# TPS_buckboost.net
KiCad netlist of a schematic drawn in Altium Designer
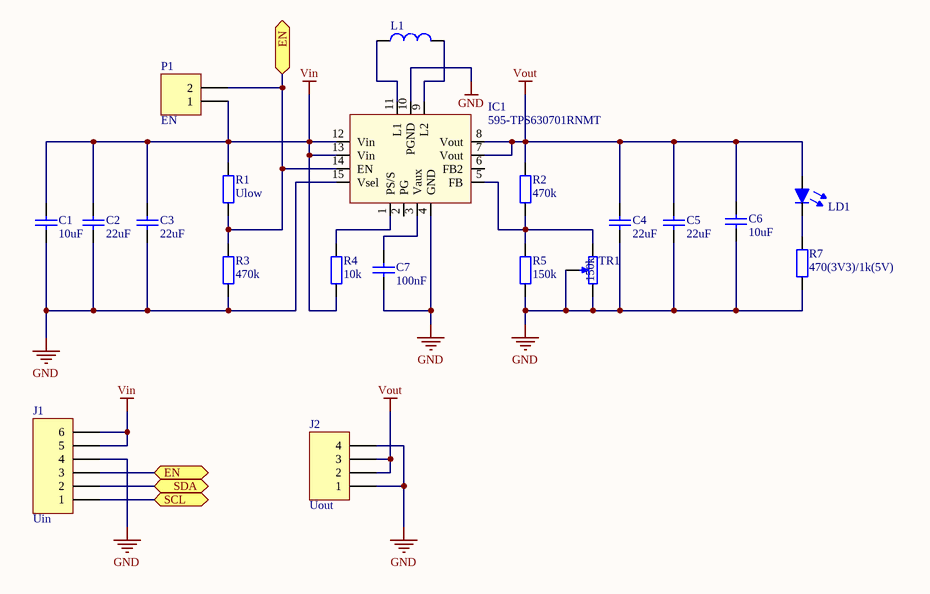
[diagram p0: TPS buckboost.SchDoc]

(export (version "E")
  (design (tool "Eeschema 10.0.6"))
  (components
    (comp (ref "C1")
      (value "10uF")
      (footprint "0805 CAP")
      (description "Capacitor")
      (fields (field (name "VOLTAGE") "10V"))
      (libsource (lib "IKSOR_LIB_main") (part "Capacitor NP"))
    )
    (comp (ref "C2")
      (value "22uF")
      (footprint "1210 CAP")
      (description "Capacitor")
      (fields (field (name "VOLTAGE") "10V"))
      (libsource (lib "IKSOR_LIB_main") (part "Capacitor NP"))
    )
    (comp (ref "C3")
      (value "22uF")
      (footprint "1210 CAP")
      (description "Capacitor")
      (fields (field (name "VOLTAGE") "10V"))
      (libsource (lib "IKSOR_LIB_main") (part "Capacitor NP"))
    )
    (comp (ref "C4")
      (value "22uF")
      (footprint "1210 CAP")
      (description "Capacitor NP")
      (fields (field (name "VOLTAGE") "10V") (field (name "Comment") "Capacitor"))
      (libsource (lib "IKSOR_LIB_main") (part "Capacitor NP"))
    )
    (comp (ref "C5")
      (value "22uF")
      (footprint "1210 CAP")
      (description "Capacitor NP")
      (fields (field (name "VOLTAGE") "10V") (field (name "Comment") "Capacitor"))
      (libsource (lib "IKSOR_LIB_main") (part "Capacitor NP"))
    )
    (comp (ref "C6")
      (value "10uF")
      (footprint "0805 CAP")
      (description "Capacitor")
      (libsource (lib "IKSOR_LIB_main") (part "Capacitor NP"))
    )
    (comp (ref "C7")
      (value "100nF")
      (footprint "0603 cap")
      (description "Capacitor")
      (fields (field (name "VOLTAGE") "10V"))
      (libsource (lib "IKSOR_LIB_main") (part "Capacitor NP"))
    )
    (comp (ref "IC1")
      (value "TPS63070/71")
      (footprint "VQFN TPS")
      (description "Buck-boost switcher")
      (fields (field (name "SUPPLIER PART NUMBER 1") "595-TPS630701RNMT"))
      (libsource (lib "IKSOR_LIB_main") (part "TPS63070/71"))
    )
    (comp (ref "J1")
      (value "Uin")
      (footprint "HDR1X6")
      (description "Header, 6-Pin")
      (fields (field (name "PUBLISHER") "Altium Limited"))
      (libsource (lib "Miscellaneous Connectors") (part "Header 6"))
    )
    (comp (ref "J2")
      (value "Uout")
      (footprint "HDR1X4")
      (description "Header, 4-Pin")
      (fields (field (name "PUBLISHER") "Altium Limited"))
      (libsource (lib "Miscellaneous Connectors") (part "Header 4"))
    )
    (comp (ref "L1")
      (value "Inductor")
      (footprint "FDSD0420-H")
      (description "Single coil")
      (libsource (lib "IKSOR_LIB_main") (part "Inductor"))
    )
    (comp (ref "LD1")
      (value "LED diode")
      (footprint "LED_0603")
      (description "LED")
      (libsource (lib "IKSOR_LIB_main") (part "LED diode"))
    )
    (comp (ref "P1")
      (value "EN")
      (footprint "HDR1X2")
      (description "Header, 2-Pin")
      (libsource (lib "Miscellaneous Connectors") (part "Header 2"))
    )
    (comp (ref "R1")
      (value "Ulow")
      (footprint "0603 RES")
      (description "NP")
      (fields (field (name "Comment") "Resistor generic"))
      (libsource (lib "IKSOR_LIB_main") (part "Resistor"))
    )
    (comp (ref "R2")
      (value "470k")
      (footprint "0603 RES")
      (description "Resistor SMD")
      (fields (field (name "Comment") "Resistor generic"))
      (libsource (lib "IKSOR_LIB_main") (part "Resistor"))
    )
    (comp (ref "R3")
      (value "470k")
      (footprint "0603 RES")
      (description "Resistor SMD")
      (fields (field (name "Comment") "Resistor generic"))
      (libsource (lib "IKSOR_LIB_main") (part "Resistor"))
    )
    (comp (ref "R4")
      (value "10k")
      (footprint "0603 RES")
      (description "Resistor SMD")
      (fields (field (name "Comment") "Resistor generic"))
      (libsource (lib "IKSOR_LIB_main") (part "Resistor"))
    )
    (comp (ref "R5")
      (value "150k")
      (footprint "0603 RES")
      (description "Resistor SMD")
      (fields (field (name "Comment") "Resistor generic"))
      (libsource (lib "IKSOR_LIB_main") (part "Resistor"))
    )
    (comp (ref "R7")
      (value "470(3V3)/1k(5V)")
      (footprint "0603 RES")
      (description "Resistor SMD")
      (fields (field (name "Comment") "Resistor generic"))
      (libsource (lib "IKSOR_LIB_main") (part "Resistor"))
    )
    (comp (ref "TR1")
      (value "150k")
      (footprint "Multiturn 1")
      (description "Trimmer")
      (fields (field (name "Comment") "NP"))
      (libsource (lib "IKSOR_LIB_main") (part "Resistor_trim"))
    )
  )
  (nets
    (net (code "1") (name "/EN") (class "Default")
      (node (ref "IC1") (pin "14") (pinfunction "EN_14") (pintype "passive"))
      (node (ref "J1") (pin "3") (pinfunction "3_3") (pintype "passive"))
      (node (ref "P1") (pin "2") (pinfunction "2_2") (pintype "passive"))
      (node (ref "R1") (pin "1") (pinfunction "1_1") (pintype "passive"))
      (node (ref "R3") (pin "2") (pinfunction "2_2") (pintype "passive"))
    )
    (net (code "2") (name "/SCL") (class "Default")
      (node (ref "J1") (pin "1") (pinfunction "1_1") (pintype "passive"))
    )
    (net (code "3") (name "/SDA") (class "Default")
      (node (ref "J1") (pin "2") (pinfunction "2_2") (pintype "passive"))
    )
    (net (code "4") (name "GND") (class "Default")
      (node (ref "C1") (pin "2") (pinfunction "2_2") (pintype "passive"))
      (node (ref "C2") (pin "1") (pinfunction "1_1") (pintype "passive"))
      (node (ref "C3") (pin "1") (pinfunction "1_1") (pintype "passive"))
      (node (ref "C4") (pin "1") (pinfunction "1_1") (pintype "passive"))
      (node (ref "C5") (pin "1") (pinfunction "1_1") (pintype "passive"))
      (node (ref "C6") (pin "2") (pinfunction "2_2") (pintype "passive"))
      (node (ref "C7") (pin "1") (pinfunction "1_1") (pintype "passive"))
      (node (ref "IC1") (pin "10") (pinfunction "PGND_10") (pintype "passive"))
      (node (ref "IC1") (pin "15") (pinfunction "Vsel_15") (pintype "passive"))
      (node (ref "IC1") (pin "4") (pinfunction "GND_4") (pintype "passive"))
      (node (ref "J1") (pin "4") (pinfunction "4_4") (pintype "passive"))
      (node (ref "J2") (pin "1") (pinfunction "1_1") (pintype "passive"))
      (node (ref "J2") (pin "4") (pinfunction "4_4") (pintype "passive"))
      (node (ref "R3") (pin "1") (pinfunction "1_1") (pintype "passive"))
      (node (ref "R5") (pin "1") (pinfunction "1_1") (pintype "passive"))
      (node (ref "R7") (pin "1") (pinfunction "1_1") (pintype "passive"))
      (node (ref "TR1") (pin "2") (pinfunction "BOT_2") (pintype "passive"))
      (node (ref "TR1") (pin "3") (pinfunction "TAP_3") (pintype "passive"))
    )
    (net (code "5") (name "Net-(IC1-FB)") (class "Default")
      (node (ref "IC1") (pin "5") (pinfunction "FB_5") (pintype "passive"))
      (node (ref "R2") (pin "1") (pinfunction "1_1") (pintype "passive"))
      (node (ref "R5") (pin "2") (pinfunction "2_2") (pintype "passive"))
      (node (ref "TR1") (pin "1") (pinfunction "TOP_1") (pintype "passive"))
    )
    (net (code "6") (name "Net-(IC1-L1)") (class "Default")
      (node (ref "IC1") (pin "11") (pinfunction "L1_11") (pintype "passive"))
      (node (ref "L1") (pin "1") (pinfunction "1_1") (pintype "passive"))
    )
    (net (code "7") (name "Net-(IC1-L2)") (class "Default")
      (node (ref "IC1") (pin "9") (pinfunction "L2_9") (pintype "passive"))
      (node (ref "L1") (pin "2") (pinfunction "2_2") (pintype "passive"))
    )
    (net (code "8") (name "Net-(IC1-PS{slash}S)") (class "Default")
      (node (ref "IC1") (pin "1") (pinfunction "PS/S_1") (pintype "passive"))
      (node (ref "R4") (pin "2") (pinfunction "2_2") (pintype "passive"))
    )
    (net (code "9") (name "Net-(IC1-Vaux)") (class "Default")
      (node (ref "C7") (pin "2") (pinfunction "2_2") (pintype "passive"))
      (node (ref "IC1") (pin "3") (pinfunction "Vaux_3") (pintype "passive"))
    )
    (net (code "10") (name "Net-(LD1-K)") (class "Default")
      (node (ref "LD1") (pin "2") (pinfunction "K_2") (pintype "passive"))
      (node (ref "R7") (pin "2") (pinfunction "2_2") (pintype "passive"))
    )
    (net (code "11") (name "Vin") (class "Default")
      (node (ref "C1") (pin "1") (pinfunction "1_1") (pintype "passive"))
      (node (ref "C2") (pin "2") (pinfunction "2_2") (pintype "passive"))
      (node (ref "C3") (pin "2") (pinfunction "2_2") (pintype "passive"))
      (node (ref "IC1") (pin "12") (pinfunction "Vin_12") (pintype "passive"))
      (node (ref "IC1") (pin "13") (pinfunction "Vin_13") (pintype "passive"))
      (node (ref "J1") (pin "5") (pinfunction "5_5") (pintype "passive"))
      (node (ref "J1") (pin "6") (pinfunction "6_6") (pintype "passive"))
      (node (ref "P1") (pin "1") (pinfunction "1_1") (pintype "passive"))
      (node (ref "R1") (pin "2") (pinfunction "2_2") (pintype "passive"))
      (node (ref "R4") (pin "1") (pinfunction "1_1") (pintype "passive"))
    )
    (net (code "12") (name "Vout") (class "Default")
      (node (ref "C4") (pin "2") (pinfunction "2_2") (pintype "passive"))
      (node (ref "C5") (pin "2") (pinfunction "2_2") (pintype "passive"))
      (node (ref "C6") (pin "1") (pinfunction "1_1") (pintype "passive"))
      (node (ref "IC1") (pin "7") (pinfunction "Vout_7") (pintype "passive"))
      (node (ref "IC1") (pin "8") (pinfunction "Vout_8") (pintype "passive"))
      (node (ref "J2") (pin "2") (pinfunction "2_2") (pintype "passive"))
      (node (ref "J2") (pin "3") (pinfunction "3_3") (pintype "passive"))
      (node (ref "LD1") (pin "1") (pinfunction "A1_1") (pintype "passive"))
      (node (ref "R2") (pin "2") (pinfunction "2_2") (pintype "passive"))
    )
    (net (code "13") (name "unconnected-(IC1-FB2-Pad6)") (class "Default")
      (node (ref "IC1") (pin "6") (pinfunction "FB2_6") (pintype "passive"))
    )
    (net (code "14") (name "unconnected-(IC1-PG-Pad2)") (class "Default")
      (node (ref "IC1") (pin "2") (pinfunction "PG_2") (pintype "passive"))
    )
  )
)
